# ADC_Channels.net
KiCad netlist of a schematic drawn in Altium Designer
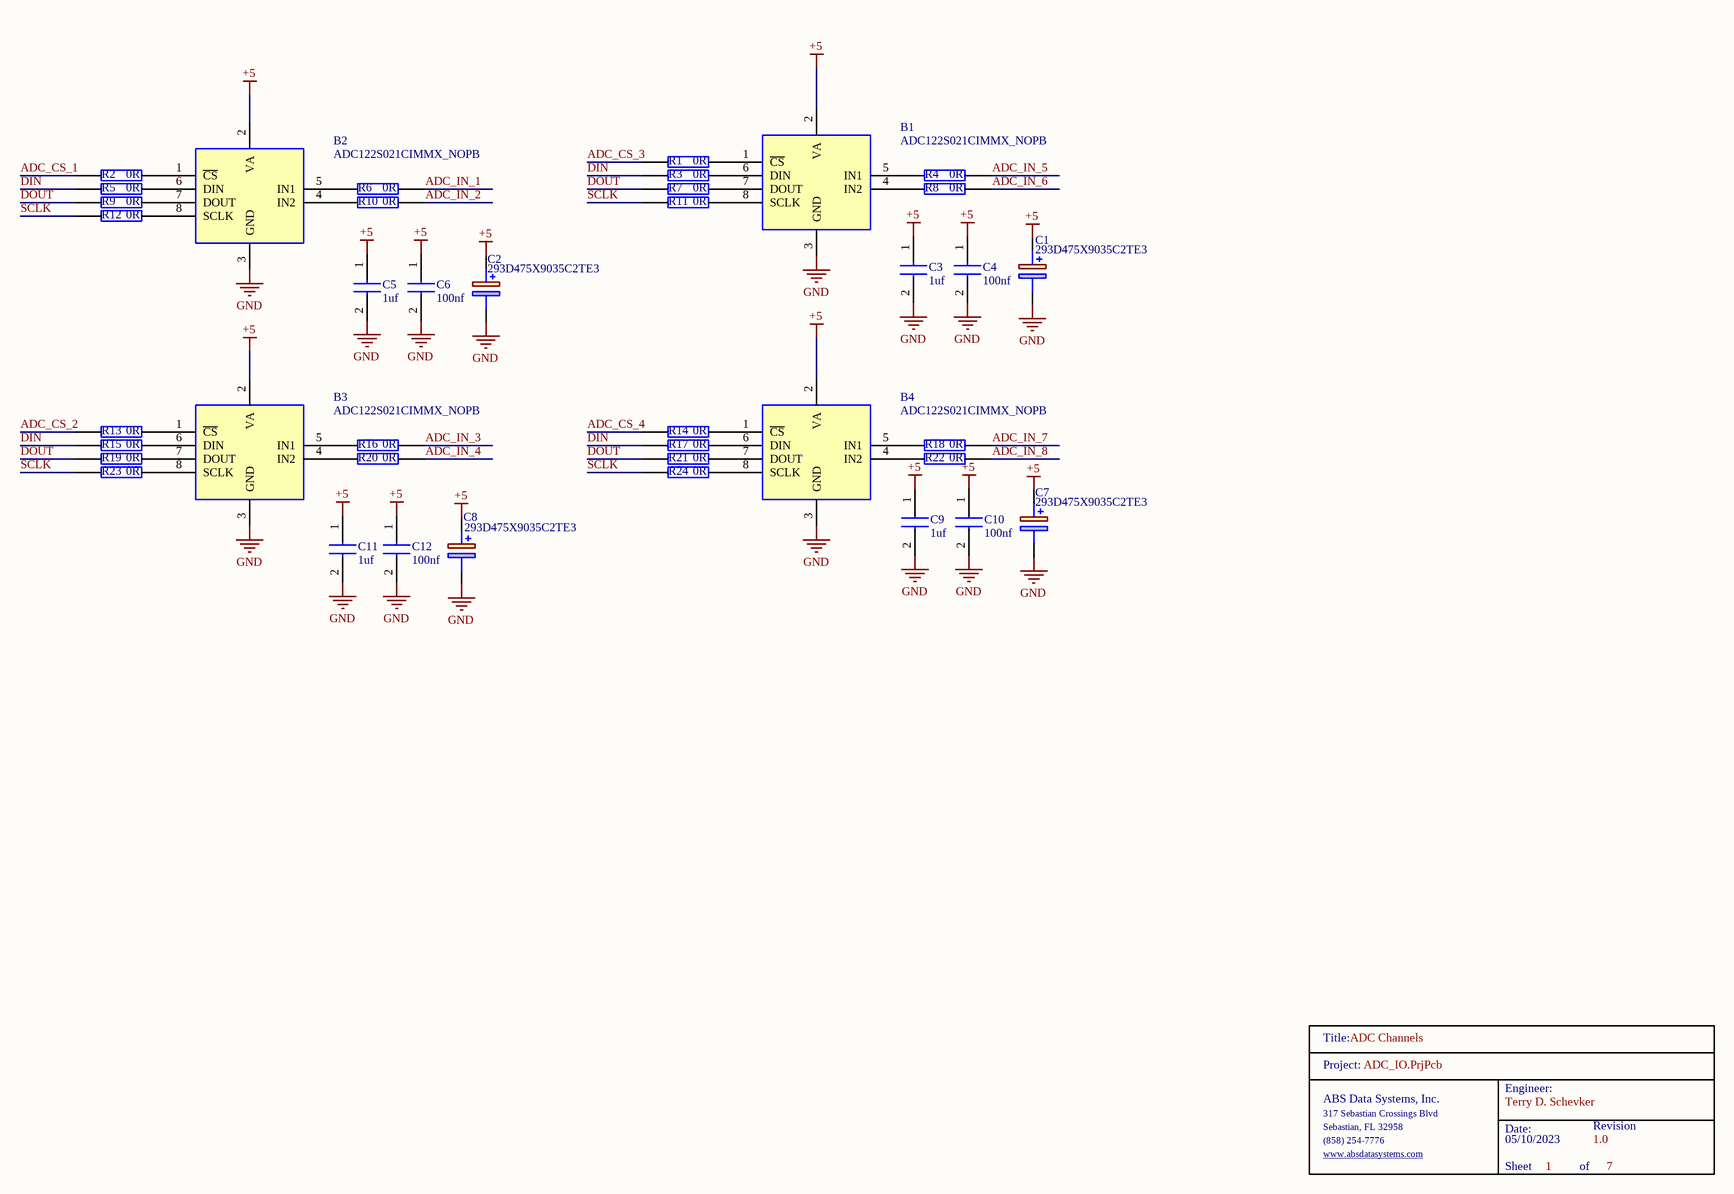
[diagram p0: ADC_Channels.SchDoc]

(export (version "E")
  (design (tool "Eeschema 10.0.6"))
  (components
    (comp (ref "B1")
      (value "ADC122S021CIMMX_NOPB")
      (footprint "SOP65P490X110-8N")
      (description "2 Channel, 50 ksps to 200 ksps 12-Bit A/D Converter")
      (fields
        (field (name "MOUSER PART NUMBER") "926-A122S021CIMMXNPB")
        (field (name "MANUFACTURER_PART_NUMBER") "ADC122S021CIMMX/NOPB")
      )
      (libsource (lib "SemiConductors") (part "ADC122S021CIMMX_NOPB"))
    )
    (comp (ref "B2")
      (value "ADC122S021CIMMX_NOPB")
      (footprint "SOP65P490X110-8N")
      (description "2 Channel, 50 ksps to 200 ksps 12-Bit A/D Converter")
      (fields
        (field (name "MOUSER PART NUMBER") "926-A122S021CIMMXNPB")
        (field (name "MANUFACTURER_PART_NUMBER") "ADC122S021CIMMX/NOPB")
      )
      (libsource (lib "SemiConductors") (part "ADC122S021CIMMX_NOPB"))
    )
    (comp (ref "B3")
      (value "ADC122S021CIMMX_NOPB")
      (footprint "SOP65P490X110-8N")
      (description "2 Channel, 50 ksps to 200 ksps 12-Bit A/D Converter")
      (fields
        (field (name "MOUSER PART NUMBER") "926-A122S021CIMMXNPB")
        (field (name "MANUFACTURER_PART_NUMBER") "ADC122S021CIMMX/NOPB")
      )
      (libsource (lib "SemiConductors") (part "ADC122S021CIMMX_NOPB"))
    )
    (comp (ref "B4")
      (value "ADC122S021CIMMX_NOPB")
      (footprint "SOP65P490X110-8N")
      (description "2 Channel, 50 ksps to 200 ksps 12-Bit A/D Converter")
      (fields
        (field (name "MOUSER PART NUMBER") "926-A122S021CIMMXNPB")
        (field (name "MANUFACTURER_PART_NUMBER") "ADC122S021CIMMX/NOPB")
      )
      (libsource (lib "SemiConductors") (part "ADC122S021CIMMX_NOPB"))
    )
    (comp (ref "C1")
      (value "293D475X9035C2TE3")
      (footprint "CAPPM6032X280N")
      (fields (field (name "MOUSER PART NUMBER") "74-293D475X9035C2TE3"))
      (libsource (lib "Capacitors") (part "293D475X9035C2TE3"))
    )
    (comp (ref "C2")
      (value "293D475X9035C2TE3")
      (footprint "CAPPM6032X280N")
      (fields (field (name "MOUSER PART NUMBER") "74-293D475X9035C2TE3"))
      (libsource (lib "Capacitors") (part "293D475X9035C2TE3"))
    )
    (comp (ref "C3")
      (value "1uf")
      (footprint "0603")
      (description "Samsung Electro-Mechanics 0603 1uf")
      (libsource (lib "Capacitors") (part "CL10B105KA8NNNL"))
    )
    (comp (ref "C4")
      (value "100nf")
      (footprint "0603")
      (description "Samsung Electro-Mechanics 0603 100nf")
      (libsource (lib "Capacitors") (part "CL10B104JB8NNNC"))
    )
    (comp (ref "C5")
      (value "1uf")
      (footprint "0603")
      (description "Samsung Electro-Mechanics 0603 1uf")
      (libsource (lib "Capacitors") (part "CL10B105KA8NNNL"))
    )
    (comp (ref "C6")
      (value "100nf")
      (footprint "0603")
      (description "Samsung Electro-Mechanics 0603 100nf")
      (libsource (lib "Capacitors") (part "CL10B104JB8NNNC"))
    )
    (comp (ref "C7")
      (value "293D475X9035C2TE3")
      (footprint "CAPPM6032X280N")
      (fields (field (name "MOUSER PART NUMBER") "74-293D475X9035C2TE3"))
      (libsource (lib "Capacitors") (part "293D475X9035C2TE3"))
    )
    (comp (ref "C8")
      (value "293D475X9035C2TE3")
      (footprint "CAPPM6032X280N")
      (fields (field (name "MOUSER PART NUMBER") "74-293D475X9035C2TE3"))
      (libsource (lib "Capacitors") (part "293D475X9035C2TE3"))
    )
    (comp (ref "C9")
      (value "1uf")
      (footprint "0603")
      (description "Samsung Electro-Mechanics 0603 1uf")
      (libsource (lib "Capacitors") (part "CL10B105KA8NNNL"))
    )
    (comp (ref "C10")
      (value "100nf")
      (footprint "0603")
      (description "Samsung Electro-Mechanics 0603 100nf")
      (libsource (lib "Capacitors") (part "CL10B104JB8NNNC"))
    )
    (comp (ref "C11")
      (value "1uf")
      (footprint "0603")
      (description "Samsung Electro-Mechanics 0603 1uf")
      (libsource (lib "Capacitors") (part "CL10B105KA8NNNL"))
    )
    (comp (ref "C12")
      (value "100nf")
      (footprint "0603")
      (description "Samsung Electro-Mechanics 0603 100nf")
      (libsource (lib "Capacitors") (part "CL10B104JB8NNNC"))
    )
    (comp (ref "R1")
      (value "0R")
      (footprint "0603")
      (description "YAGEO 0603 0 ohm")
      (fields
        (field (name "MOUSER PART NUMBER") "603-RC0603JR-070RL")
        (field (name "MANUFACTURER_PART_NUMBER") "RC0603JR-070RL")
      )
      (libsource (lib "Resistors") (part "RC0603JR-070RL"))
    )
    (comp (ref "R2")
      (value "0R")
      (footprint "0603")
      (description "YAGEO 0603 0 ohm")
      (fields
        (field (name "MOUSER PART NUMBER") "603-RC0603JR-070RL")
        (field (name "MANUFACTURER_PART_NUMBER") "RC0603JR-070RL")
      )
      (libsource (lib "Resistors") (part "RC0603JR-070RL"))
    )
    (comp (ref "R3")
      (value "0R")
      (footprint "0603")
      (description "YAGEO 0603 0 ohm")
      (fields
        (field (name "MOUSER PART NUMBER") "603-RC0603JR-070RL")
        (field (name "MANUFACTURER_PART_NUMBER") "RC0603JR-070RL")
      )
      (libsource (lib "Resistors") (part "RC0603JR-070RL"))
    )
    (comp (ref "R4")
      (value "0R")
      (footprint "0603")
      (description "YAGEO 0603 0 ohm")
      (fields
        (field (name "MOUSER PART NUMBER") "603-RC0603JR-070RL")
        (field (name "MANUFACTURER_PART_NUMBER") "RC0603JR-070RL")
      )
      (libsource (lib "Resistors") (part "RC0603JR-070RL"))
    )
    (comp (ref "R5")
      (value "0R")
      (footprint "0603")
      (description "YAGEO 0603 0 ohm")
      (fields
        (field (name "MOUSER PART NUMBER") "603-RC0603JR-070RL")
        (field (name "MANUFACTURER_PART_NUMBER") "RC0603JR-070RL")
      )
      (libsource (lib "Resistors") (part "RC0603JR-070RL"))
    )
    (comp (ref "R6")
      (value "0R")
      (footprint "0603")
      (description "YAGEO 0603 0 ohm")
      (fields
        (field (name "MOUSER PART NUMBER") "603-RC0603JR-070RL")
        (field (name "MANUFACTURER_PART_NUMBER") "RC0603JR-070RL")
      )
      (libsource (lib "Resistors") (part "RC0603JR-070RL"))
    )
    (comp (ref "R7")
      (value "0R")
      (footprint "0603")
      (description "YAGEO 0603 0 ohm")
      (fields
        (field (name "MOUSER PART NUMBER") "603-RC0603JR-070RL")
        (field (name "MANUFACTURER_PART_NUMBER") "RC0603JR-070RL")
      )
      (libsource (lib "Resistors") (part "RC0603JR-070RL"))
    )
    (comp (ref "R8")
      (value "0R")
      (footprint "0603")
      (description "YAGEO 0603 0 ohm")
      (fields
        (field (name "MOUSER PART NUMBER") "603-RC0603JR-070RL")
        (field (name "MANUFACTURER_PART_NUMBER") "RC0603JR-070RL")
      )
      (libsource (lib "Resistors") (part "RC0603JR-070RL"))
    )
    (comp (ref "R9")
      (value "0R")
      (footprint "0603")
      (description "YAGEO 0603 0 ohm")
      (fields
        (field (name "MOUSER PART NUMBER") "603-RC0603JR-070RL")
        (field (name "MANUFACTURER_PART_NUMBER") "RC0603JR-070RL")
      )
      (libsource (lib "Resistors") (part "RC0603JR-070RL"))
    )
    (comp (ref "R10")
      (value "0R")
      (footprint "0603")
      (description "YAGEO 0603 0 ohm")
      (fields
        (field (name "MOUSER PART NUMBER") "603-RC0603JR-070RL")
        (field (name "MANUFACTURER_PART_NUMBER") "RC0603JR-070RL")
      )
      (libsource (lib "Resistors") (part "RC0603JR-070RL"))
    )
    (comp (ref "R11")
      (value "0R")
      (footprint "0603")
      (description "YAGEO 0603 0 ohm")
      (fields
        (field (name "MOUSER PART NUMBER") "603-RC0603JR-070RL")
        (field (name "MANUFACTURER_PART_NUMBER") "RC0603JR-070RL")
      )
      (libsource (lib "Resistors") (part "RC0603JR-070RL"))
    )
    (comp (ref "R12")
      (value "0R")
      (footprint "0603")
      (description "YAGEO 0603 0 ohm")
      (fields
        (field (name "MOUSER PART NUMBER") "603-RC0603JR-070RL")
        (field (name "MANUFACTURER_PART_NUMBER") "RC0603JR-070RL")
      )
      (libsource (lib "Resistors") (part "RC0603JR-070RL"))
    )
    (comp (ref "R13")
      (value "0R")
      (footprint "0603")
      (description "YAGEO 0603 0 ohm")
      (fields
        (field (name "MOUSER PART NUMBER") "603-RC0603JR-070RL")
        (field (name "MANUFACTURER_PART_NUMBER") "RC0603JR-070RL")
      )
      (libsource (lib "Resistors") (part "RC0603JR-070RL"))
    )
    (comp (ref "R14")
      (value "0R")
      (footprint "0603")
      (description "YAGEO 0603 0 ohm")
      (fields
        (field (name "MOUSER PART NUMBER") "603-RC0603JR-070RL")
        (field (name "MANUFACTURER_PART_NUMBER") "RC0603JR-070RL")
      )
      (libsource (lib "Resistors") (part "RC0603JR-070RL"))
    )
    (comp (ref "R15")
      (value "0R")
      (footprint "0603")
      (description "YAGEO 0603 0 ohm")
      (fields
        (field (name "MOUSER PART NUMBER") "603-RC0603JR-070RL")
        (field (name "MANUFACTURER_PART_NUMBER") "RC0603JR-070RL")
      )
      (libsource (lib "Resistors") (part "RC0603JR-070RL"))
    )
    (comp (ref "R16")
      (value "0R")
      (footprint "0603")
      (description "YAGEO 0603 0 ohm")
      (fields
        (field (name "MOUSER PART NUMBER") "603-RC0603JR-070RL")
        (field (name "MANUFACTURER_PART_NUMBER") "RC0603JR-070RL")
      )
      (libsource (lib "Resistors") (part "RC0603JR-070RL"))
    )
    (comp (ref "R17")
      (value "0R")
      (footprint "0603")
      (description "YAGEO 0603 0 ohm")
      (fields
        (field (name "MOUSER PART NUMBER") "603-RC0603JR-070RL")
        (field (name "MANUFACTURER_PART_NUMBER") "RC0603JR-070RL")
      )
      (libsource (lib "Resistors") (part "RC0603JR-070RL"))
    )
    (comp (ref "R18")
      (value "0R")
      (footprint "0603")
      (description "YAGEO 0603 0 ohm")
      (fields
        (field (name "MOUSER PART NUMBER") "603-RC0603JR-070RL")
        (field (name "MANUFACTURER_PART_NUMBER") "RC0603JR-070RL")
      )
      (libsource (lib "Resistors") (part "RC0603JR-070RL"))
    )
    (comp (ref "R19")
      (value "0R")
      (footprint "0603")
      (description "YAGEO 0603 0 ohm")
      (fields
        (field (name "MOUSER PART NUMBER") "603-RC0603JR-070RL")
        (field (name "MANUFACTURER_PART_NUMBER") "RC0603JR-070RL")
      )
      (libsource (lib "Resistors") (part "RC0603JR-070RL"))
    )
    (comp (ref "R20")
      (value "0R")
      (footprint "0603")
      (description "YAGEO 0603 0 ohm")
      (fields
        (field (name "MOUSER PART NUMBER") "603-RC0603JR-070RL")
        (field (name "MANUFACTURER_PART_NUMBER") "RC0603JR-070RL")
      )
      (libsource (lib "Resistors") (part "RC0603JR-070RL"))
    )
    (comp (ref "R21")
      (value "0R")
      (footprint "0603")
      (description "YAGEO 0603 0 ohm")
      (fields
        (field (name "MOUSER PART NUMBER") "603-RC0603JR-070RL")
        (field (name "MANUFACTURER_PART_NUMBER") "RC0603JR-070RL")
      )
      (libsource (lib "Resistors") (part "RC0603JR-070RL"))
    )
    (comp (ref "R22")
      (value "0R")
      (footprint "0603")
      (description "YAGEO 0603 0 ohm")
      (fields
        (field (name "MOUSER PART NUMBER") "603-RC0603JR-070RL")
        (field (name "MANUFACTURER_PART_NUMBER") "RC0603JR-070RL")
      )
      (libsource (lib "Resistors") (part "RC0603JR-070RL"))
    )
    (comp (ref "R23")
      (value "0R")
      (footprint "0603")
      (description "YAGEO 0603 0 ohm")
      (fields
        (field (name "MOUSER PART NUMBER") "603-RC0603JR-070RL")
        (field (name "MANUFACTURER_PART_NUMBER") "RC0603JR-070RL")
      )
      (libsource (lib "Resistors") (part "RC0603JR-070RL"))
    )
    (comp (ref "R24")
      (value "0R")
      (footprint "0603")
      (description "YAGEO 0603 0 ohm")
      (fields
        (field (name "MOUSER PART NUMBER") "603-RC0603JR-070RL")
        (field (name "MANUFACTURER_PART_NUMBER") "RC0603JR-070RL")
      )
      (libsource (lib "Resistors") (part "RC0603JR-070RL"))
    )
    (comp (ref "TitleBlock_1") (value "TitleBlock") (libsource (lib "Misc") (part "TitleBlock")))
  )
  (nets
    (net (code "1") (name "+5") (class "Default")
      (node (ref "B1") (pin "2") (pinfunction "VA_2") (pintype "passive"))
      (node (ref "B2") (pin "2") (pinfunction "VA_2") (pintype "passive"))
      (node (ref "B3") (pin "2") (pinfunction "VA_2") (pintype "passive"))
      (node (ref "B4") (pin "2") (pinfunction "VA_2") (pintype "passive"))
      (node (ref "C1") (pin "1") (pinfunction "+_1") (pintype "passive"))
      (node (ref "C10") (pin "1") (pinfunction "1_1") (pintype "passive"))
      (node (ref "C11") (pin "1") (pinfunction "1_1") (pintype "passive"))
      (node (ref "C12") (pin "1") (pinfunction "1_1") (pintype "passive"))
      (node (ref "C2") (pin "1") (pinfunction "+_1") (pintype "passive"))
      (node (ref "C3") (pin "1") (pinfunction "1_1") (pintype "passive"))
      (node (ref "C4") (pin "1") (pinfunction "1_1") (pintype "passive"))
      (node (ref "C5") (pin "1") (pinfunction "1_1") (pintype "passive"))
      (node (ref "C6") (pin "1") (pinfunction "1_1") (pintype "passive"))
      (node (ref "C7") (pin "1") (pinfunction "+_1") (pintype "passive"))
      (node (ref "C8") (pin "1") (pinfunction "+_1") (pintype "passive"))
      (node (ref "C9") (pin "1") (pinfunction "1_1") (pintype "passive"))
    )
    (net (code "2") (name "/ADC_CS_1") (class "Default")
      (node (ref "R2") (pin "1") (pinfunction "1_1") (pintype "passive"))
    )
    (net (code "3") (name "/ADC_CS_2") (class "Default")
      (node (ref "R13") (pin "1") (pinfunction "1_1") (pintype "passive"))
    )
    (net (code "4") (name "/ADC_CS_3") (class "Default")
      (node (ref "R1") (pin "1") (pinfunction "1_1") (pintype "passive"))
    )
    (net (code "5") (name "/ADC_CS_4") (class "Default")
      (node (ref "R14") (pin "1") (pinfunction "1_1") (pintype "passive"))
    )
    (net (code "6") (name "/ADC_IN_1") (class "Default")
      (node (ref "R6") (pin "2") (pinfunction "2_2") (pintype "passive"))
    )
    (net (code "7") (name "/ADC_IN_2") (class "Default")
      (node (ref "R10") (pin "2") (pinfunction "2_2") (pintype "passive"))
    )
    (net (code "8") (name "/ADC_IN_3") (class "Default")
      (node (ref "R16") (pin "2") (pinfunction "2_2") (pintype "passive"))
    )
    (net (code "9") (name "/ADC_IN_4") (class "Default")
      (node (ref "R20") (pin "2") (pinfunction "2_2") (pintype "passive"))
    )
    (net (code "10") (name "/ADC_IN_5") (class "Default")
      (node (ref "R4") (pin "2") (pinfunction "2_2") (pintype "passive"))
    )
    (net (code "11") (name "/ADC_IN_6") (class "Default")
      (node (ref "R8") (pin "2") (pinfunction "2_2") (pintype "passive"))
    )
    (net (code "12") (name "/ADC_IN_7") (class "Default")
      (node (ref "R18") (pin "2") (pinfunction "2_2") (pintype "passive"))
    )
    (net (code "13") (name "/ADC_IN_8") (class "Default")
      (node (ref "R22") (pin "2") (pinfunction "2_2") (pintype "passive"))
    )
    (net (code "14") (name "/DIN") (class "Default")
      (node (ref "R15") (pin "1") (pinfunction "1_1") (pintype "passive"))
      (node (ref "R17") (pin "1") (pinfunction "1_1") (pintype "passive"))
      (node (ref "R3") (pin "1") (pinfunction "1_1") (pintype "passive"))
      (node (ref "R5") (pin "1") (pinfunction "1_1") (pintype "passive"))
    )
    (net (code "15") (name "/DOUT") (class "Default")
      (node (ref "R19") (pin "1") (pinfunction "1_1") (pintype "passive"))
      (node (ref "R21") (pin "1") (pinfunction "1_1") (pintype "passive"))
      (node (ref "R7") (pin "1") (pinfunction "1_1") (pintype "passive"))
      (node (ref "R9") (pin "1") (pinfunction "1_1") (pintype "passive"))
    )
    (net (code "16") (name "/SCLK") (class "Default")
      (node (ref "R11") (pin "1") (pinfunction "1_1") (pintype "passive"))
      (node (ref "R12") (pin "1") (pinfunction "1_1") (pintype "passive"))
      (node (ref "R23") (pin "1") (pinfunction "1_1") (pintype "passive"))
      (node (ref "R24") (pin "1") (pinfunction "1_1") (pintype "passive"))
    )
    (net (code "17") (name "GND") (class "Default")
      (node (ref "B1") (pin "3") (pinfunction "GND_3") (pintype "passive"))
      (node (ref "B2") (pin "3") (pinfunction "GND_3") (pintype "passive"))
      (node (ref "B3") (pin "3") (pinfunction "GND_3") (pintype "passive"))
      (node (ref "B4") (pin "3") (pinfunction "GND_3") (pintype "passive"))
      (node (ref "C1") (pin "2") (pinfunction "-_2") (pintype "passive"))
      (node (ref "C10") (pin "2") (pinfunction "2_2") (pintype "passive"))
      (node (ref "C11") (pin "2") (pinfunction "2_2") (pintype "passive"))
      (node (ref "C12") (pin "2") (pinfunction "2_2") (pintype "passive"))
      (node (ref "C2") (pin "2") (pinfunction "-_2") (pintype "passive"))
      (node (ref "C3") (pin "2") (pinfunction "2_2") (pintype "passive"))
      (node (ref "C4") (pin "2") (pinfunction "2_2") (pintype "passive"))
      (node (ref "C5") (pin "2") (pinfunction "2_2") (pintype "passive"))
      (node (ref "C6") (pin "2") (pinfunction "2_2") (pintype "passive"))
      (node (ref "C7") (pin "2") (pinfunction "-_2") (pintype "passive"))
      (node (ref "C8") (pin "2") (pinfunction "-_2") (pintype "passive"))
      (node (ref "C9") (pin "2") (pinfunction "2_2") (pintype "passive"))
    )
    (net (code "18") (name "Net-(B1-DIN)") (class "Default")
      (node (ref "B1") (pin "6") (pinfunction "DIN_6") (pintype "passive"))
      (node (ref "R3") (pin "2") (pinfunction "2_2") (pintype "passive"))
    )
    (net (code "19") (name "Net-(B1-DOUT)") (class "Default")
      (node (ref "B1") (pin "7") (pinfunction "DOUT_7") (pintype "passive"))
      (node (ref "R7") (pin "2") (pinfunction "2_2") (pintype "passive"))
    )
    (net (code "20") (name "Net-(B1-IN1)") (class "Default")
      (node (ref "B1") (pin "5") (pinfunction "IN1_5") (pintype "passive"))
      (node (ref "R4") (pin "1") (pinfunction "1_1") (pintype "passive"))
    )
    (net (code "21") (name "Net-(B1-IN2)") (class "Default")
      (node (ref "B1") (pin "4") (pinfunction "IN2_4") (pintype "passive"))
      (node (ref "R8") (pin "1") (pinfunction "1_1") (pintype "passive"))
    )
    (net (code "22") (name "Net-(B1-SCLK)") (class "Default")
      (node (ref "B1") (pin "8") (pinfunction "SCLK_8") (pintype "passive"))
      (node (ref "R11") (pin "2") (pinfunction "2_2") (pintype "passive"))
    )
    (net (code "23") (name "Net-(B1-~{CS})") (class "Default")
      (node (ref "B1") (pin "1") (pinfunction "~{CS}_1") (pintype "passive"))
      (node (ref "R1") (pin "2") (pinfunction "2_2") (pintype "passive"))
    )
    (net (code "24") (name "Net-(B2-DIN)") (class "Default")
      (node (ref "B2") (pin "6") (pinfunction "DIN_6") (pintype "passive"))
      (node (ref "R5") (pin "2") (pinfunction "2_2") (pintype "passive"))
    )
    (net (code "25") (name "Net-(B2-DOUT)") (class "Default")
      (node (ref "B2") (pin "7") (pinfunction "DOUT_7") (pintype "passive"))
      (node (ref "R9") (pin "2") (pinfunction "2_2") (pintype "passive"))
    )
    (net (code "26") (name "Net-(B2-IN1)") (class "Default")
      (node (ref "B2") (pin "5") (pinfunction "IN1_5") (pintype "passive"))
      (node (ref "R6") (pin "1") (pinfunction "1_1") (pintype "passive"))
    )
    (net (code "27") (name "Net-(B2-IN2)") (class "Default")
      (node (ref "B2") (pin "4") (pinfunction "IN2_4") (pintype "passive"))
      (node (ref "R10") (pin "1") (pinfunction "1_1") (pintype "passive"))
    )
    (net (code "28") (name "Net-(B2-SCLK)") (class "Default")
      (node (ref "B2") (pin "8") (pinfunction "SCLK_8") (pintype "passive"))
      (node (ref "R12") (pin "2") (pinfunction "2_2") (pintype "passive"))
    )
    (net (code "29") (name "Net-(B2-~{CS})") (class "Default")
      (node (ref "B2") (pin "1") (pinfunction "~{CS}_1") (pintype "passive"))
      (node (ref "R2") (pin "2") (pinfunction "2_2") (pintype "passive"))
    )
    (net (code "30") (name "Net-(B3-DIN)") (class "Default")
      (node (ref "B3") (pin "6") (pinfunction "DIN_6") (pintype "passive"))
      (node (ref "R15") (pin "2") (pinfunction "2_2") (pintype "passive"))
    )
    (net (code "31") (name "Net-(B3-DOUT)") (class "Default")
      (node (ref "B3") (pin "7") (pinfunction "DOUT_7") (pintype "passive"))
      (node (ref "R19") (pin "2") (pinfunction "2_2") (pintype "passive"))
    )
    (net (code "32") (name "Net-(B3-IN1)") (class "Default")
      (node (ref "B3") (pin "5") (pinfunction "IN1_5") (pintype "passive"))
      (node (ref "R16") (pin "1") (pinfunction "1_1") (pintype "passive"))
    )
    (net (code "33") (name "Net-(B3-IN2)") (class "Default")
      (node (ref "B3") (pin "4") (pinfunction "IN2_4") (pintype "passive"))
      (node (ref "R20") (pin "1") (pinfunction "1_1") (pintype "passive"))
    )
    (net (code "34") (name "Net-(B3-SCLK)") (class "Default")
      (node (ref "B3") (pin "8") (pinfunction "SCLK_8") (pintype "passive"))
      (node (ref "R23") (pin "2") (pinfunction "2_2") (pintype "passive"))
    )
    (net (code "35") (name "Net-(B3-~{CS})") (class "Default")
      (node (ref "B3") (pin "1") (pinfunction "~{CS}_1") (pintype "passive"))
      (node (ref "R13") (pin "2") (pinfunction "2_2") (pintype "passive"))
    )
    (net (code "36") (name "Net-(B4-DIN)") (class "Default")
      (node (ref "B4") (pin "6") (pinfunction "DIN_6") (pintype "passive"))
      (node (ref "R17") (pin "2") (pinfunction "2_2") (pintype "passive"))
    )
    (net (code "37") (name "Net-(B4-DOUT)") (class "Default")
      (node (ref "B4") (pin "7") (pinfunction "DOUT_7") (pintype "passive"))
      (node (ref "R21") (pin "2") (pinfunction "2_2") (pintype "passive"))
    )
    (net (code "38") (name "Net-(B4-IN1)") (class "Default")
      (node (ref "B4") (pin "5") (pinfunction "IN1_5") (pintype "passive"))
      (node (ref "R18") (pin "1") (pinfunction "1_1") (pintype "passive"))
    )
    (net (code "39") (name "Net-(B4-IN2)") (class "Default")
      (node (ref "B4") (pin "4") (pinfunction "IN2_4") (pintype "passive"))
      (node (ref "R22") (pin "1") (pinfunction "1_1") (pintype "passive"))
    )
    (net (code "40") (name "Net-(B4-SCLK)") (class "Default")
      (node (ref "B4") (pin "8") (pinfunction "SCLK_8") (pintype "passive"))
      (node (ref "R24") (pin "2") (pinfunction "2_2") (pintype "passive"))
    )
    (net (code "41") (name "Net-(B4-~{CS})") (class "Default")
      (node (ref "B4") (pin "1") (pinfunction "~{CS}_1") (pintype "passive"))
      (node (ref "R14") (pin "2") (pinfunction "2_2") (pintype "passive"))
    )
  )
)
